# DFPLayerAudio.net
KiCad netlist of a schematic drawn in EAGLE
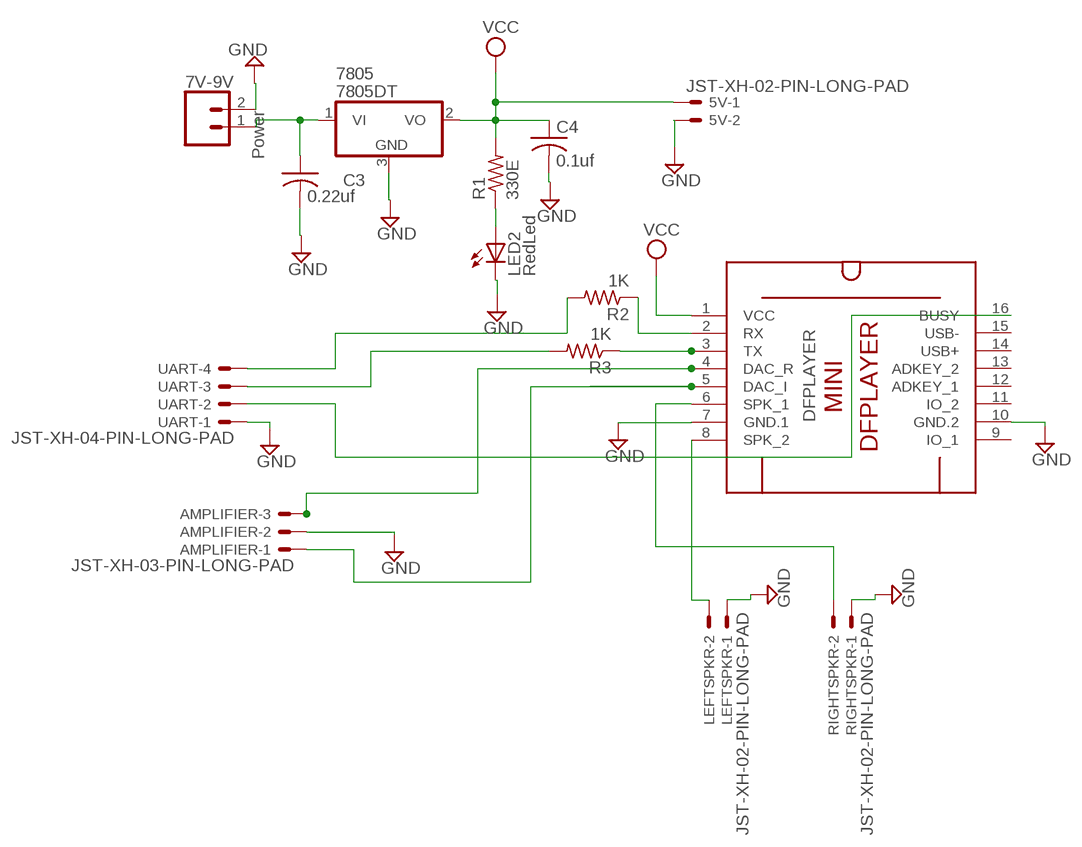
[diagram p0: schematic, sheet 1]

(export (version "E")
  (design (tool "Eeschema 10.0.6"))
  (components
    (comp (ref "5V")
      (value "JST-XH-02-PIN-LONG-PAD")
      (footprint "eagle-import:JST-XH-02-PACKAGE-LONG-PAD")
      (libsource (lib "eagle-import") (part "JST-XH-02-PIN-LONG-PAD"))
    )
    (comp (ref "7V-9V")
      (value "Power")
      (footprint "eagle-import:SCREWTERMINAL-5MM-2")
      (libsource (lib "eagle-import") (part "CONN_025MM"))
    )
    (comp (ref "7805")
      (value "7805DT")
      (footprint "eagle-import:TO252")
      (libsource (lib "eagle-import") (part "78DT05"))
    )
    (comp (ref "AMPLIFIER")
      (value "JST-XH-03-PIN-LONG-PAD")
      (footprint "eagle-import:JST-XH-03-PACKAGE-LONG-PAD")
      (libsource (lib "eagle-import") (part "JST-XH-03-PIN-LONG-PAD"))
    )
    (comp (ref "C3")
      (value "0.22uf")
      (footprint "eagle-import:C0805K")
      (libsource (lib "eagle-import") (part "C-USC0805K"))
    )
    (comp (ref "C4")
      (value "0.1uf")
      (footprint "eagle-import:C0805K")
      (libsource (lib "eagle-import") (part "C-USC0805K"))
    )
    (comp (ref "DFPLAYER")
      (value "DFPLAYER-MINI-MODULE")
      (footprint "eagle-import:DFPLAYER-MINI-MODULE")
      (libsource (lib "eagle-import") (part "DFPLAYER-MINI-MODULE"))
    )
    (comp (ref "LED2")
      (value "RedLed")
      (footprint "eagle-import:CHIPLED_0805")
      (libsource (lib "eagle-import") (part "LEDCHIPLED_0805"))
    )
    (comp (ref "LEFTSPKR")
      (value "JST-XH-02-PIN-LONG-PAD")
      (footprint "eagle-import:JST-XH-02-PACKAGE-LONG-PAD")
      (libsource (lib "eagle-import") (part "JST-XH-02-PIN-LONG-PAD"))
    )
    (comp (ref "R1")
      (value "330E")
      (footprint "eagle-import:M0805")
      (libsource (lib "eagle-import") (part "R-US_M0805"))
    )
    (comp (ref "R2")
      (value "1K")
      (footprint "eagle-import:M0805")
      (libsource (lib "eagle-import") (part "R-US_M0805"))
    )
    (comp (ref "R3")
      (value "1K")
      (footprint "eagle-import:M0805")
      (libsource (lib "eagle-import") (part "R-US_M0805"))
    )
    (comp (ref "RIGHTSPKR")
      (value "JST-XH-02-PIN-LONG-PAD")
      (footprint "eagle-import:JST-XH-02-PACKAGE-LONG-PAD")
      (libsource (lib "eagle-import") (part "JST-XH-02-PIN-LONG-PAD"))
    )
    (comp (ref "UART")
      (value "JST-XH-04-PIN-LONG-PAD")
      (footprint "eagle-import:JST-XH-04-PACKAGE-LONG-PAD")
      (libsource (lib "eagle-import") (part "JST-XH-04-PIN-LONG-PAD"))
    )
  )
  (nets
    (net (code "1") (name "GND") (class "Default")
      (node (ref "5V") (pin "2") (pinfunction "S_2") (pintype "passive"))
      (node (ref "7805") (pin "3") (pinfunction "GND_3") (pintype "passive"))
      (node (ref "7V-9V") (pin "2") (pinfunction "2_2") (pintype "passive"))
      (node (ref "AMPLIFIER") (pin "2") (pinfunction "S_2") (pintype "passive"))
      (node (ref "C3") (pin "2") (pinfunction "2_2") (pintype "passive"))
      (node (ref "C4") (pin "2") (pinfunction "2_2") (pintype "passive"))
      (node (ref "DFPLAYER") (pin "10") (pinfunction "GND.2_10") (pintype "power_in"))
      (node (ref "DFPLAYER") (pin "7") (pinfunction "GND.1_7") (pintype "power_in"))
      (node (ref "LED2") (pin "C") (pinfunction "C_C") (pintype "passive"))
      (node (ref "LEFTSPKR") (pin "1") (pinfunction "S_1") (pintype "passive"))
      (node (ref "RIGHTSPKR") (pin "1") (pinfunction "S_1") (pintype "passive"))
      (node (ref "UART") (pin "1") (pinfunction "S_1") (pintype "passive"))
    )
    (net (code "2") (name "Net-(7805-VI)") (class "Default")
      (node (ref "7805") (pin "1") (pinfunction "VI_1") (pintype "input"))
      (node (ref "7V-9V") (pin "1") (pinfunction "1_1") (pintype "passive"))
      (node (ref "C3") (pin "1") (pinfunction "1_1") (pintype "passive"))
    )
    (net (code "3") (name "Net-(AMPLIFIERA-S)") (class "Default")
      (node (ref "AMPLIFIER") (pin "1") (pinfunction "S_1") (pintype "passive"))
      (node (ref "DFPLAYER") (pin "5") (pinfunction "DAC_I_5") (pintype "bidirectional"))
    )
    (net (code "4") (name "Net-(AMPLIFIERC-S)") (class "Default")
      (node (ref "AMPLIFIER") (pin "3") (pinfunction "S_3") (pintype "passive"))
      (node (ref "DFPLAYER") (pin "4") (pinfunction "DAC_R_4") (pintype "bidirectional"))
    )
    (net (code "5") (name "Net-(DFPLAYER-BUSY)") (class "Default")
      (node (ref "DFPLAYER") (pin "16") (pinfunction "BUSY_16") (pintype "bidirectional"))
      (node (ref "UART") (pin "2") (pinfunction "S_2") (pintype "passive"))
    )
    (net (code "6") (name "Net-(DFPLAYER-RX)") (class "Default")
      (node (ref "DFPLAYER") (pin "2") (pinfunction "RX_2") (pintype "bidirectional"))
      (node (ref "R2") (pin "1") (pinfunction "1_1") (pintype "passive"))
    )
    (net (code "7") (name "Net-(DFPLAYER-SPK_1)") (class "Default")
      (node (ref "DFPLAYER") (pin "6") (pinfunction "SPK_1_6") (pintype "bidirectional"))
      (node (ref "RIGHTSPKR") (pin "2") (pinfunction "S_2") (pintype "passive"))
    )
    (net (code "8") (name "Net-(DFPLAYER-SPK_2)") (class "Default")
      (node (ref "DFPLAYER") (pin "8") (pinfunction "SPK_2_8") (pintype "bidirectional"))
      (node (ref "LEFTSPKR") (pin "2") (pinfunction "S_2") (pintype "passive"))
    )
    (net (code "9") (name "Net-(DFPLAYER-TX)") (class "Default")
      (node (ref "DFPLAYER") (pin "3") (pinfunction "TX_3") (pintype "bidirectional"))
      (node (ref "R3") (pin "1") (pinfunction "1_1") (pintype "passive"))
    )
    (net (code "10") (name "Net-(LED2-PadA)") (class "Default")
      (node (ref "LED2") (pin "A") (pinfunction "A_A") (pintype "passive"))
      (node (ref "R1") (pin "1") (pinfunction "1_1") (pintype "passive"))
    )
    (net (code "11") (name "Net-(UARTC-S)") (class "Default")
      (node (ref "R3") (pin "2") (pinfunction "2_2") (pintype "passive"))
      (node (ref "UART") (pin "3") (pinfunction "S_3") (pintype "passive"))
    )
    (net (code "12") (name "Net-(UARTD-S)") (class "Default")
      (node (ref "R2") (pin "2") (pinfunction "2_2") (pintype "passive"))
      (node (ref "UART") (pin "4") (pinfunction "S_4") (pintype "passive"))
    )
    (net (code "13") (name "VCC") (class "Default")
      (node (ref "5V") (pin "1") (pinfunction "S_1") (pintype "passive"))
      (node (ref "7805") (pin "2") (pinfunction "VO_2") (pintype "passive"))
      (node (ref "C4") (pin "1") (pinfunction "1_1") (pintype "passive"))
      (node (ref "DFPLAYER") (pin "1") (pinfunction "VCC_1") (pintype "power_in"))
      (node (ref "R1") (pin "2") (pinfunction "2_2") (pintype "passive"))
    )
    (net (code "14") (name "unconnected-(DFPLAYER-ADKEY_1-Pad12)") (class "Default")
      (node (ref "DFPLAYER") (pin "12") (pinfunction "ADKEY_1_12") (pintype "bidirectional"))
    )
    (net (code "15") (name "unconnected-(DFPLAYER-ADKEY_2-Pad13)") (class "Default")
      (node (ref "DFPLAYER") (pin "13") (pinfunction "ADKEY_2_13") (pintype "bidirectional"))
    )
    (net (code "16") (name "unconnected-(DFPLAYER-IO_1-Pad9)") (class "Default")
      (node (ref "DFPLAYER") (pin "9") (pinfunction "IO_1_9") (pintype "bidirectional"))
    )
    (net (code "17") (name "unconnected-(DFPLAYER-IO_2-Pad11)") (class "Default")
      (node (ref "DFPLAYER") (pin "11") (pinfunction "IO_2_11") (pintype "bidirectional"))
    )
    (net (code "18") (name "unconnected-(DFPLAYER-USB+-Pad14)") (class "Default")
      (node (ref "DFPLAYER") (pin "14") (pinfunction "USB+_14") (pintype "bidirectional"))
    )
    (net (code "19") (name "unconnected-(DFPLAYER-USB--Pad15)") (class "Default")
      (node (ref "DFPLAYER") (pin "15") (pinfunction "USB-_15") (pintype "bidirectional"))
    )
  )
)
